# Arduinp-Shield-MicroPunch.net
KiCad netlist of a schematic drawn in EAGLE
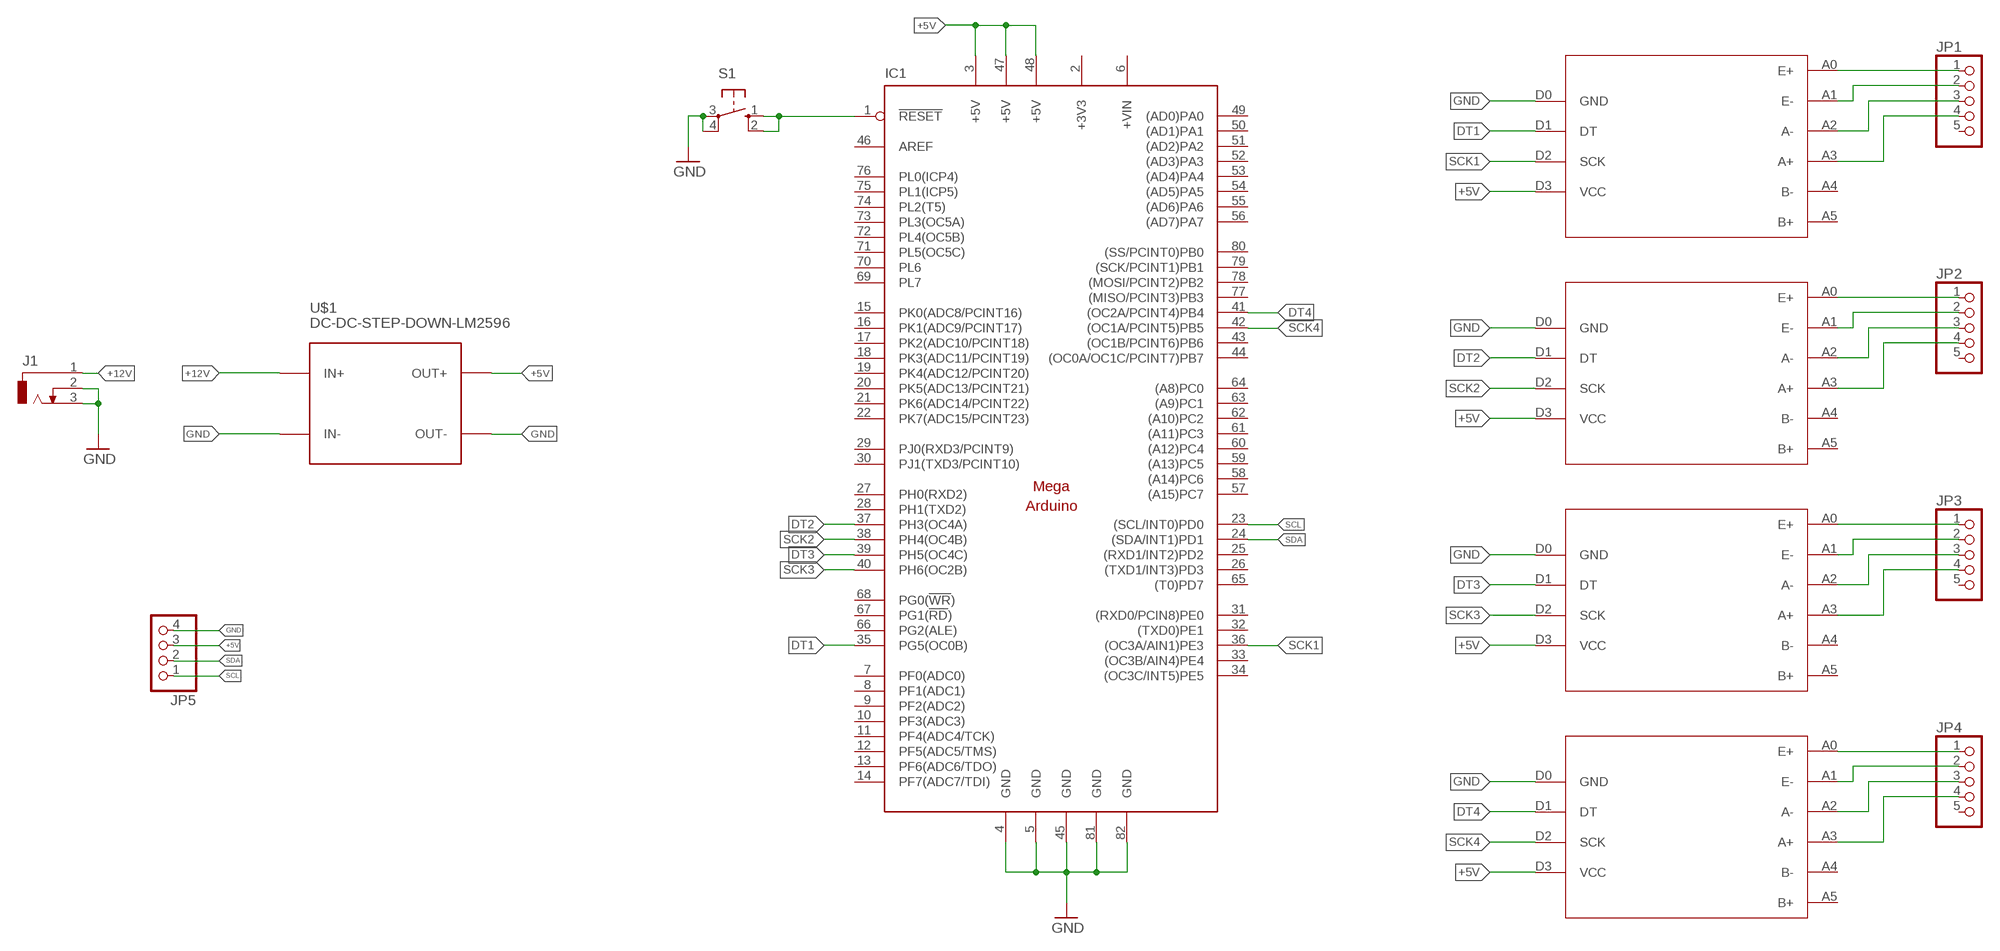
[diagram p0: schematic, sheet 1]

(export (version "E")
  (design (tool "Eeschema 10.0.6"))
  (components
    (comp (ref "IC1")
      (value "MEGAARDUINO_11")
      (footprint "eagle-import:MEGA_ARDUINO_1")
      (libsource (lib "eagle-import") (part "MEGAARDUINO_11"))
    )
    (comp (ref "J1")
      (value "DCJ0303")
      (footprint "eagle-import:DCJ0303")
      (libsource (lib "eagle-import") (part "DCJ0303"))
    )
    (comp (ref "JP1")
      (value "PINHD-1X5")
      (footprint "eagle-import:1X05")
      (libsource (lib "eagle-import") (part "PINHD-1X5"))
    )
    (comp (ref "JP2")
      (value "PINHD-1X5")
      (footprint "eagle-import:1X05")
      (libsource (lib "eagle-import") (part "PINHD-1X5"))
    )
    (comp (ref "JP3")
      (value "PINHD-1X5")
      (footprint "eagle-import:1X05")
      (libsource (lib "eagle-import") (part "PINHD-1X5"))
    )
    (comp (ref "JP4")
      (value "PINHD-1X5")
      (footprint "eagle-import:1X05")
      (libsource (lib "eagle-import") (part "PINHD-1X5"))
    )
    (comp (ref "JP5")
      (value "PINHD-1X4")
      (footprint "eagle-import:1X04")
      (libsource (lib "eagle-import") (part "PINHD-1X4"))
    )
    (comp (ref "S1")
      (value "10-XX")
      (footprint "eagle-import:B3F-10XX")
      (fields (field (name "MPN") "B3F-1000"))
      (libsource (lib "eagle-import") (part "10-XX"))
    )
    (comp (ref "SM1")
      (value "HX711")
      (footprint "eagle-import:HX711")
      (libsource (lib "eagle-import") (part "HX711"))
    )
    (comp (ref "SM2")
      (value "HX711")
      (footprint "eagle-import:HX711")
      (libsource (lib "eagle-import") (part "HX711"))
    )
    (comp (ref "SM3")
      (value "HX711")
      (footprint "eagle-import:HX711")
      (libsource (lib "eagle-import") (part "HX711"))
    )
    (comp (ref "SM4")
      (value "HX711")
      (footprint "eagle-import:HX711")
      (libsource (lib "eagle-import") (part "HX711"))
    )
    (comp (ref "U$1")
      (value "DC-DC-STEP-DOWN-LM2596")
      (footprint "eagle-import:DC-DC-STEP-DOWN-LM2596")
      (libsource (lib "eagle-import") (part "DC-DC-STEP-DOWN-LM2596"))
    )
  )
  (nets
    (net (code "1") (name "+5V") (class "Default")
      (node (ref "IC1") (pin "3") (pinfunction "+5V_3") (pintype "power_in"))
      (node (ref "IC1") (pin "47") (pinfunction "+5V_47") (pintype "power_in"))
      (node (ref "IC1") (pin "48") (pinfunction "+5V_48") (pintype "power_in"))
      (node (ref "JP5") (pin "3") (pinfunction "3_3") (pintype "passive"))
      (node (ref "SM1") (pin "D3") (pinfunction "VCC_D3") (pintype "bidirectional"))
      (node (ref "SM2") (pin "D3") (pinfunction "VCC_D3") (pintype "bidirectional"))
      (node (ref "SM3") (pin "D3") (pinfunction "VCC_D3") (pintype "bidirectional"))
      (node (ref "SM4") (pin "D3") (pinfunction "VCC_D3") (pintype "bidirectional"))
      (node (ref "U$1") (pin "OUT+") (pinfunction "OUT+_OUT+") (pintype "bidirectional"))
    )
    (net (code "2") (name "+12V") (class "Default")
      (node (ref "J1") (pin "1") (pinfunction "1_1") (pintype "passive"))
      (node (ref "U$1") (pin "IN+") (pinfunction "IN+_IN+") (pintype "bidirectional"))
    )
    (net (code "3") (name "/+3V3") (class "Default")
      (node (ref "IC1") (pin "2") (pinfunction "+3V3_2") (pintype "power_in"))
    )
    (net (code "4") (name "/+VIN") (class "Default")
      (node (ref "IC1") (pin "6") (pinfunction "+VIN_6") (pintype "power_in"))
    )
    (net (code "5") (name "DT1") (class "Default")
      (node (ref "IC1") (pin "35") (pinfunction "PG5(OC0B)_35") (pintype "bidirectional"))
      (node (ref "SM1") (pin "D1") (pinfunction "DT_D1") (pintype "bidirectional"))
    )
    (net (code "6") (name "DT2") (class "Default")
      (node (ref "IC1") (pin "37") (pinfunction "PH3(OC4A)_37") (pintype "bidirectional"))
      (node (ref "SM2") (pin "D1") (pinfunction "DT_D1") (pintype "bidirectional"))
    )
    (net (code "7") (name "DT3") (class "Default")
      (node (ref "IC1") (pin "39") (pinfunction "PH5(OC4C)_39") (pintype "bidirectional"))
      (node (ref "SM3") (pin "D1") (pinfunction "DT_D1") (pintype "bidirectional"))
    )
    (net (code "8") (name "DT4") (class "Default")
      (node (ref "IC1") (pin "41") (pinfunction "(OC2A/PCINT4)PB4_41") (pintype "bidirectional"))
      (node (ref "SM4") (pin "D1") (pinfunction "DT_D1") (pintype "bidirectional"))
    )
    (net (code "9") (name "GND") (class "Default")
      (node (ref "IC1") (pin "4") (pinfunction "GND_4") (pintype "power_in"))
      (node (ref "IC1") (pin "45") (pinfunction "GND_45") (pintype "power_in"))
      (node (ref "IC1") (pin "5") (pinfunction "GND_5") (pintype "power_in"))
      (node (ref "IC1") (pin "81") (pinfunction "GND_81") (pintype "power_in"))
      (node (ref "IC1") (pin "82") (pinfunction "GND_82") (pintype "power_in"))
      (node (ref "J1") (pin "2") (pinfunction "2_2") (pintype "passive"))
      (node (ref "J1") (pin "3") (pinfunction "3_3") (pintype "passive"))
      (node (ref "JP5") (pin "4") (pinfunction "4_4") (pintype "passive"))
      (node (ref "S1") (pin "3") (pinfunction "P_3") (pintype "passive"))
      (node (ref "S1") (pin "4") (pinfunction "P1_4") (pintype "passive"))
      (node (ref "SM1") (pin "D0") (pinfunction "GND_D0") (pintype "bidirectional"))
      (node (ref "SM2") (pin "D0") (pinfunction "GND_D0") (pintype "bidirectional"))
      (node (ref "SM3") (pin "D0") (pinfunction "GND_D0") (pintype "bidirectional"))
      (node (ref "SM4") (pin "D0") (pinfunction "GND_D0") (pintype "bidirectional"))
      (node (ref "U$1") (pin "IN-") (pinfunction "IN-_IN-") (pintype "bidirectional"))
      (node (ref "U$1") (pin "OUT-") (pinfunction "OUT-_OUT-") (pintype "bidirectional"))
    )
    (net (code "10") (name "Net-(IC1-~{RESET})") (class "Default")
      (node (ref "IC1") (pin "1") (pinfunction "~{RESET}_1") (pintype "bidirectional"))
      (node (ref "S1") (pin "1") (pinfunction "S_1") (pintype "passive"))
      (node (ref "S1") (pin "2") (pinfunction "S1_2") (pintype "passive"))
    )
    (net (code "11") (name "Net-(SM1-A+)") (class "Default")
      (node (ref "JP1") (pin "4") (pinfunction "4_4") (pintype "passive"))
      (node (ref "SM1") (pin "A3") (pinfunction "A+_A3") (pintype "bidirectional"))
    )
    (net (code "12") (name "Net-(SM1-A-)") (class "Default")
      (node (ref "JP1") (pin "3") (pinfunction "3_3") (pintype "passive"))
      (node (ref "SM1") (pin "A2") (pinfunction "A-_A2") (pintype "bidirectional"))
    )
    (net (code "13") (name "Net-(SM1-E+)") (class "Default")
      (node (ref "JP1") (pin "1") (pinfunction "1_1") (pintype "passive"))
      (node (ref "SM1") (pin "A0") (pinfunction "E+_A0") (pintype "bidirectional"))
    )
    (net (code "14") (name "Net-(SM1-E-)") (class "Default")
      (node (ref "JP1") (pin "2") (pinfunction "2_2") (pintype "passive"))
      (node (ref "SM1") (pin "A1") (pinfunction "E-_A1") (pintype "bidirectional"))
    )
    (net (code "15") (name "Net-(SM2-A+)") (class "Default")
      (node (ref "JP2") (pin "4") (pinfunction "4_4") (pintype "passive"))
      (node (ref "SM2") (pin "A3") (pinfunction "A+_A3") (pintype "bidirectional"))
    )
    (net (code "16") (name "Net-(SM2-A-)") (class "Default")
      (node (ref "JP2") (pin "3") (pinfunction "3_3") (pintype "passive"))
      (node (ref "SM2") (pin "A2") (pinfunction "A-_A2") (pintype "bidirectional"))
    )
    (net (code "17") (name "Net-(SM2-E+)") (class "Default")
      (node (ref "JP2") (pin "1") (pinfunction "1_1") (pintype "passive"))
      (node (ref "SM2") (pin "A0") (pinfunction "E+_A0") (pintype "bidirectional"))
    )
    (net (code "18") (name "Net-(SM2-E-)") (class "Default")
      (node (ref "JP2") (pin "2") (pinfunction "2_2") (pintype "passive"))
      (node (ref "SM2") (pin "A1") (pinfunction "E-_A1") (pintype "bidirectional"))
    )
    (net (code "19") (name "Net-(SM3-A+)") (class "Default")
      (node (ref "JP3") (pin "4") (pinfunction "4_4") (pintype "passive"))
      (node (ref "SM3") (pin "A3") (pinfunction "A+_A3") (pintype "bidirectional"))
    )
    (net (code "20") (name "Net-(SM3-A-)") (class "Default")
      (node (ref "JP3") (pin "3") (pinfunction "3_3") (pintype "passive"))
      (node (ref "SM3") (pin "A2") (pinfunction "A-_A2") (pintype "bidirectional"))
    )
    (net (code "21") (name "Net-(SM3-E+)") (class "Default")
      (node (ref "JP3") (pin "1") (pinfunction "1_1") (pintype "passive"))
      (node (ref "SM3") (pin "A0") (pinfunction "E+_A0") (pintype "bidirectional"))
    )
    (net (code "22") (name "Net-(SM3-E-)") (class "Default")
      (node (ref "JP3") (pin "2") (pinfunction "2_2") (pintype "passive"))
      (node (ref "SM3") (pin "A1") (pinfunction "E-_A1") (pintype "bidirectional"))
    )
    (net (code "23") (name "Net-(SM4-A+)") (class "Default")
      (node (ref "JP4") (pin "4") (pinfunction "4_4") (pintype "passive"))
      (node (ref "SM4") (pin "A3") (pinfunction "A+_A3") (pintype "bidirectional"))
    )
    (net (code "24") (name "Net-(SM4-A-)") (class "Default")
      (node (ref "JP4") (pin "3") (pinfunction "3_3") (pintype "passive"))
      (node (ref "SM4") (pin "A2") (pinfunction "A-_A2") (pintype "bidirectional"))
    )
    (net (code "25") (name "Net-(SM4-E+)") (class "Default")
      (node (ref "JP4") (pin "1") (pinfunction "1_1") (pintype "passive"))
      (node (ref "SM4") (pin "A0") (pinfunction "E+_A0") (pintype "bidirectional"))
    )
    (net (code "26") (name "Net-(SM4-E-)") (class "Default")
      (node (ref "JP4") (pin "2") (pinfunction "2_2") (pintype "passive"))
      (node (ref "SM4") (pin "A1") (pinfunction "E-_A1") (pintype "bidirectional"))
    )
    (net (code "27") (name "SCK1") (class "Default")
      (node (ref "IC1") (pin "36") (pinfunction "(OC3A/AIN1)PE3_36") (pintype "bidirectional"))
      (node (ref "SM1") (pin "D2") (pinfunction "SCK_D2") (pintype "bidirectional"))
    )
    (net (code "28") (name "SCK2") (class "Default")
      (node (ref "IC1") (pin "38") (pinfunction "PH4(OC4B)_38") (pintype "bidirectional"))
      (node (ref "SM2") (pin "D2") (pinfunction "SCK_D2") (pintype "bidirectional"))
    )
    (net (code "29") (name "SCK3") (class "Default")
      (node (ref "IC1") (pin "40") (pinfunction "PH6(OC2B)_40") (pintype "bidirectional"))
      (node (ref "SM3") (pin "D2") (pinfunction "SCK_D2") (pintype "bidirectional"))
    )
    (net (code "30") (name "SCK4") (class "Default")
      (node (ref "IC1") (pin "42") (pinfunction "(OC1A/PCINT5)PB5_42") (pintype "bidirectional"))
      (node (ref "SM4") (pin "D2") (pinfunction "SCK_D2") (pintype "bidirectional"))
    )
    (net (code "31") (name "SCL") (class "Default")
      (node (ref "IC1") (pin "23") (pinfunction "(SCL/INT0)PD0_23") (pintype "bidirectional"))
      (node (ref "JP5") (pin "1") (pinfunction "1_1") (pintype "passive"))
    )
    (net (code "32") (name "SDA") (class "Default")
      (node (ref "IC1") (pin "24") (pinfunction "(SDA/INT1)PD1_24") (pintype "bidirectional"))
      (node (ref "JP5") (pin "2") (pinfunction "2_2") (pintype "passive"))
    )
    (net (code "33") (name "unconnected-(IC1-(A8)PC0-Pad64)") (class "Default")
      (node (ref "IC1") (pin "64") (pinfunction "(A8)PC0_64") (pintype "bidirectional"))
    )
    (net (code "34") (name "unconnected-(IC1-(A9)PC1-Pad63)") (class "Default")
      (node (ref "IC1") (pin "63") (pinfunction "(A9)PC1_63") (pintype "bidirectional"))
    )
    (net (code "35") (name "unconnected-(IC1-(A10)PC2-Pad62)") (class "Default")
      (node (ref "IC1") (pin "62") (pinfunction "(A10)PC2_62") (pintype "bidirectional"))
    )
    (net (code "36") (name "unconnected-(IC1-(A11)PC3-Pad61)") (class "Default")
      (node (ref "IC1") (pin "61") (pinfunction "(A11)PC3_61") (pintype "bidirectional"))
    )
    (net (code "37") (name "unconnected-(IC1-(A12)PC4-Pad60)") (class "Default")
      (node (ref "IC1") (pin "60") (pinfunction "(A12)PC4_60") (pintype "bidirectional"))
    )
    (net (code "38") (name "unconnected-(IC1-(A13)PC5-Pad59)") (class "Default")
      (node (ref "IC1") (pin "59") (pinfunction "(A13)PC5_59") (pintype "bidirectional"))
    )
    (net (code "39") (name "unconnected-(IC1-(A14)PC6-Pad58)") (class "Default")
      (node (ref "IC1") (pin "58") (pinfunction "(A14)PC6_58") (pintype "bidirectional"))
    )
    (net (code "40") (name "unconnected-(IC1-(A15)PC7-Pad57)") (class "Default")
      (node (ref "IC1") (pin "57") (pinfunction "(A15)PC7_57") (pintype "bidirectional"))
    )
    (net (code "41") (name "unconnected-(IC1-(AD0)PA0-Pad49)") (class "Default")
      (node (ref "IC1") (pin "49") (pinfunction "(AD0)PA0_49") (pintype "bidirectional"))
    )
    (net (code "42") (name "unconnected-(IC1-(AD1)PA1-Pad50)") (class "Default")
      (node (ref "IC1") (pin "50") (pinfunction "(AD1)PA1_50") (pintype "bidirectional"))
    )
    (net (code "43") (name "unconnected-(IC1-(AD2)PA2-Pad51)") (class "Default")
      (node (ref "IC1") (pin "51") (pinfunction "(AD2)PA2_51") (pintype "bidirectional"))
    )
    (net (code "44") (name "unconnected-(IC1-(AD3)PA3-Pad52)") (class "Default")
      (node (ref "IC1") (pin "52") (pinfunction "(AD3)PA3_52") (pintype "bidirectional"))
    )
    (net (code "45") (name "unconnected-(IC1-(AD4)PA4-Pad53)") (class "Default")
      (node (ref "IC1") (pin "53") (pinfunction "(AD4)PA4_53") (pintype "bidirectional"))
    )
    (net (code "46") (name "unconnected-(IC1-(AD5)PA5-Pad54)") (class "Default")
      (node (ref "IC1") (pin "54") (pinfunction "(AD5)PA5_54") (pintype "bidirectional"))
    )
    (net (code "47") (name "unconnected-(IC1-(AD6)PA6-Pad55)") (class "Default")
      (node (ref "IC1") (pin "55") (pinfunction "(AD6)PA6_55") (pintype "bidirectional"))
    )
    (net (code "48") (name "unconnected-(IC1-(AD7)PA7-Pad56)") (class "Default")
      (node (ref "IC1") (pin "56") (pinfunction "(AD7)PA7_56") (pintype "bidirectional"))
    )
    (net (code "49") (name "unconnected-(IC1-(MISO{slash}PCINT3)PB3-Pad77)") (class "Default")
      (node (ref "IC1") (pin "77") (pinfunction "(MISO/PCINT3)PB3_77") (pintype "bidirectional"))
    )
    (net (code "50") (name "unconnected-(IC1-(MOSI{slash}PCINT2)PB2-Pad78)") (class "Default")
      (node (ref "IC1") (pin "78") (pinfunction "(MOSI/PCINT2)PB2_78") (pintype "bidirectional"))
    )
    (net (code "51") (name "unconnected-(IC1-(OC0A{slash}OC1C{slash}PCINT7)PB7-Pad44)") (class "Default")
      (node (ref "IC1") (pin "44") (pinfunction "(OC0A/OC1C/PCINT7)PB7_44") (pintype "bidirectional"))
    )
    (net (code "52") (name "unconnected-(IC1-(OC1B{slash}PCINT6)PB6-Pad43)") (class "Default")
      (node (ref "IC1") (pin "43") (pinfunction "(OC1B/PCINT6)PB6_43") (pintype "bidirectional"))
    )
    (net (code "53") (name "unconnected-(IC1-(OC3B{slash}AIN4)PE4-Pad33)") (class "Default")
      (node (ref "IC1") (pin "33") (pinfunction "(OC3B/AIN4)PE4_33") (pintype "bidirectional"))
    )
    (net (code "54") (name "unconnected-(IC1-(OC3C{slash}INT5)PE5-Pad34)") (class "Default")
      (node (ref "IC1") (pin "34") (pinfunction "(OC3C/INT5)PE5_34") (pintype "bidirectional"))
    )
    (net (code "55") (name "unconnected-(IC1-(RXD0{slash}PCIN8)PE0-Pad31)") (class "Default")
      (node (ref "IC1") (pin "31") (pinfunction "(RXD0/PCIN8)PE0_31") (pintype "bidirectional"))
    )
    (net (code "56") (name "unconnected-(IC1-(RXD1{slash}INT2)PD2-Pad25)") (class "Default")
      (node (ref "IC1") (pin "25") (pinfunction "(RXD1/INT2)PD2_25") (pintype "bidirectional"))
    )
    (net (code "57") (name "unconnected-(IC1-(SCK{slash}PCINT1)PB1-Pad79)") (class "Default")
      (node (ref "IC1") (pin "79") (pinfunction "(SCK/PCINT1)PB1_79") (pintype "bidirectional"))
    )
    (net (code "58") (name "unconnected-(IC1-(SS{slash}PCINT0)PB0-Pad80)") (class "Default")
      (node (ref "IC1") (pin "80") (pinfunction "(SS/PCINT0)PB0_80") (pintype "bidirectional"))
    )
    (net (code "59") (name "unconnected-(IC1-(T0)PD7-Pad65)") (class "Default")
      (node (ref "IC1") (pin "65") (pinfunction "(T0)PD7_65") (pintype "bidirectional"))
    )
    (net (code "60") (name "unconnected-(IC1-(TXD0)PE1-Pad32)") (class "Default")
      (node (ref "IC1") (pin "32") (pinfunction "(TXD0)PE1_32") (pintype "bidirectional"))
    )
    (net (code "61") (name "unconnected-(IC1-(TXD1{slash}INT3)PD3-Pad26)") (class "Default")
      (node (ref "IC1") (pin "26") (pinfunction "(TXD1/INT3)PD3_26") (pintype "bidirectional"))
    )
    (net (code "62") (name "unconnected-(IC1-AREF-Pad46)") (class "Default")
      (node (ref "IC1") (pin "46") (pinfunction "AREF_46") (pintype "bidirectional"))
    )
    (net (code "63") (name "unconnected-(IC1-PF0(ADC0)-Pad7)") (class "Default")
      (node (ref "IC1") (pin "7") (pinfunction "PF0(ADC0)_7") (pintype "bidirectional"))
    )
    (net (code "64") (name "unconnected-(IC1-PF1(ADC1)-Pad8)") (class "Default")
      (node (ref "IC1") (pin "8") (pinfunction "PF1(ADC1)_8") (pintype "bidirectional"))
    )
    (net (code "65") (name "unconnected-(IC1-PF2(ADC2)-Pad9)") (class "Default")
      (node (ref "IC1") (pin "9") (pinfunction "PF2(ADC2)_9") (pintype "bidirectional"))
    )
    (net (code "66") (name "unconnected-(IC1-PF3(ADC3)-Pad10)") (class "Default")
      (node (ref "IC1") (pin "10") (pinfunction "PF3(ADC3)_10") (pintype "bidirectional"))
    )
    (net (code "67") (name "unconnected-(IC1-PF4(ADC4{slash}TCK)-Pad11)") (class "Default")
      (node (ref "IC1") (pin "11") (pinfunction "PF4(ADC4/TCK)_11") (pintype "bidirectional"))
    )
    (net (code "68") (name "unconnected-(IC1-PF5(ADC5{slash}TMS)-Pad12)") (class "Default")
      (node (ref "IC1") (pin "12") (pinfunction "PF5(ADC5/TMS)_12") (pintype "bidirectional"))
    )
    (net (code "69") (name "unconnected-(IC1-PF6(ADC6{slash}TDO)-Pad13)") (class "Default")
      (node (ref "IC1") (pin "13") (pinfunction "PF6(ADC6/TDO)_13") (pintype "bidirectional"))
    )
    (net (code "70") (name "unconnected-(IC1-PF7(ADC7{slash}TDI)-Pad14)") (class "Default")
      (node (ref "IC1") (pin "14") (pinfunction "PF7(ADC7/TDI)_14") (pintype "bidirectional"))
    )
    (net (code "71") (name "unconnected-(IC1-PG0(~{WR})-Pad68)") (class "Default")
      (node (ref "IC1") (pin "68") (pinfunction "PG0(~{WR})_68") (pintype "bidirectional"))
    )
    (net (code "72") (name "unconnected-(IC1-PG1(~{RD})-Pad67)") (class "Default")
      (node (ref "IC1") (pin "67") (pinfunction "PG1(~{RD})_67") (pintype "bidirectional"))
    )
    (net (code "73") (name "unconnected-(IC1-PG2(ALE)-Pad66)") (class "Default")
      (node (ref "IC1") (pin "66") (pinfunction "PG2(ALE)_66") (pintype "bidirectional"))
    )
    (net (code "74") (name "unconnected-(IC1-PH0(RXD2)-Pad27)") (class "Default")
      (node (ref "IC1") (pin "27") (pinfunction "PH0(RXD2)_27") (pintype "bidirectional"))
    )
    (net (code "75") (name "unconnected-(IC1-PH1(TXD2)-Pad28)") (class "Default")
      (node (ref "IC1") (pin "28") (pinfunction "PH1(TXD2)_28") (pintype "bidirectional"))
    )
    (net (code "76") (name "unconnected-(IC1-PJ0(RXD3{slash}PCINT9)-Pad29)") (class "Default")
      (node (ref "IC1") (pin "29") (pinfunction "PJ0(RXD3/PCINT9)_29") (pintype "bidirectional"))
    )
    (net (code "77") (name "unconnected-(IC1-PJ1(TXD3{slash}PCINT10)-Pad30)") (class "Default")
      (node (ref "IC1") (pin "30") (pinfunction "PJ1(TXD3/PCINT10)_30") (pintype "bidirectional"))
    )
    (net (code "78") (name "unconnected-(IC1-PK0(ADC8{slash}PCINT16)-Pad15)") (class "Default")
      (node (ref "IC1") (pin "15") (pinfunction "PK0(ADC8/PCINT16)_15") (pintype "bidirectional"))
    )
    (net (code "79") (name "unconnected-(IC1-PK1(ADC9{slash}PCINT17)-Pad16)") (class "Default")
      (node (ref "IC1") (pin "16") (pinfunction "PK1(ADC9/PCINT17)_16") (pintype "bidirectional"))
    )
    (net (code "80") (name "unconnected-(IC1-PK2(ADC10{slash}PCINT18)-Pad17)") (class "Default")
      (node (ref "IC1") (pin "17") (pinfunction "PK2(ADC10/PCINT18)_17") (pintype "bidirectional"))
    )
    (net (code "81") (name "unconnected-(IC1-PK3(ADC11{slash}PCINT19)-Pad18)") (class "Default")
      (node (ref "IC1") (pin "18") (pinfunction "PK3(ADC11/PCINT19)_18") (pintype "bidirectional"))
    )
    (net (code "82") (name "unconnected-(IC1-PK4(ADC12{slash}PCINT20)-Pad19)") (class "Default")
      (node (ref "IC1") (pin "19") (pinfunction "PK4(ADC12/PCINT20)_19") (pintype "bidirectional"))
    )
    (net (code "83") (name "unconnected-(IC1-PK5(ADC13{slash}PCINT21)-Pad20)") (class "Default")
      (node (ref "IC1") (pin "20") (pinfunction "PK5(ADC13/PCINT21)_20") (pintype "bidirectional"))
    )
    (net (code "84") (name "unconnected-(IC1-PK6(ADC14{slash}PCINT22)-Pad21)") (class "Default")
      (node (ref "IC1") (pin "21") (pinfunction "PK6(ADC14/PCINT22)_21") (pintype "bidirectional"))
    )
    (net (code "85") (name "unconnected-(IC1-PK7(ADC15{slash}PCINT23)-Pad22)") (class "Default")
      (node (ref "IC1") (pin "22") (pinfunction "PK7(ADC15/PCINT23)_22") (pintype "bidirectional"))
    )
    (net (code "86") (name "unconnected-(IC1-PL0(ICP4)-Pad76)") (class "Default")
      (node (ref "IC1") (pin "76") (pinfunction "PL0(ICP4)_76") (pintype "bidirectional"))
    )
    (net (code "87") (name "unconnected-(IC1-PL1(ICP5)-Pad75)") (class "Default")
      (node (ref "IC1") (pin "75") (pinfunction "PL1(ICP5)_75") (pintype "bidirectional"))
    )
    (net (code "88") (name "unconnected-(IC1-PL2(T5)-Pad74)") (class "Default")
      (node (ref "IC1") (pin "74") (pinfunction "PL2(T5)_74") (pintype "bidirectional"))
    )
    (net (code "89") (name "unconnected-(IC1-PL3(OC5A)-Pad73)") (class "Default")
      (node (ref "IC1") (pin "73") (pinfunction "PL3(OC5A)_73") (pintype "bidirectional"))
    )
    (net (code "90") (name "unconnected-(IC1-PL4(OC5B)-Pad72)") (class "Default")
      (node (ref "IC1") (pin "72") (pinfunction "PL4(OC5B)_72") (pintype "bidirectional"))
    )
    (net (code "91") (name "unconnected-(IC1-PL5(OC5C)-Pad71)") (class "Default")
      (node (ref "IC1") (pin "71") (pinfunction "PL5(OC5C)_71") (pintype "bidirectional"))
    )
    (net (code "92") (name "unconnected-(IC1-PL6-Pad70)") (class "Default")
      (node (ref "IC1") (pin "70") (pinfunction "PL6_70") (pintype "bidirectional"))
    )
    (net (code "93") (name "unconnected-(IC1-PL7-Pad69)") (class "Default")
      (node (ref "IC1") (pin "69") (pinfunction "PL7_69") (pintype "bidirectional"))
    )
    (net (code "94") (name "unconnected-(JP1-Pad5)") (class "Default")
      (node (ref "JP1") (pin "5") (pinfunction "5_5") (pintype "passive"))
    )
    (net (code "95") (name "unconnected-(JP2-Pad5)") (class "Default")
      (node (ref "JP2") (pin "5") (pinfunction "5_5") (pintype "passive"))
    )
    (net (code "96") (name "unconnected-(JP3-Pad5)") (class "Default")
      (node (ref "JP3") (pin "5") (pinfunction "5_5") (pintype "passive"))
    )
    (net (code "97") (name "unconnected-(JP4-Pad5)") (class "Default")
      (node (ref "JP4") (pin "5") (pinfunction "5_5") (pintype "passive"))
    )
    (net (code "98") (name "unconnected-(SM1-B+-PadA5)") (class "Default")
      (node (ref "SM1") (pin "A5") (pinfunction "B+_A5") (pintype "bidirectional"))
    )
    (net (code "99") (name "unconnected-(SM1-B--PadA4)") (class "Default")
      (node (ref "SM1") (pin "A4") (pinfunction "B-_A4") (pintype "bidirectional"))
    )
    (net (code "100") (name "unconnected-(SM2-B+-PadA5)") (class "Default")
      (node (ref "SM2") (pin "A5") (pinfunction "B+_A5") (pintype "bidirectional"))
    )
    (net (code "101") (name "unconnected-(SM2-B--PadA4)") (class "Default")
      (node (ref "SM2") (pin "A4") (pinfunction "B-_A4") (pintype "bidirectional"))
    )
    (net (code "102") (name "unconnected-(SM3-B+-PadA5)") (class "Default")
      (node (ref "SM3") (pin "A5") (pinfunction "B+_A5") (pintype "bidirectional"))
    )
    (net (code "103") (name "unconnected-(SM3-B--PadA4)") (class "Default")
      (node (ref "SM3") (pin "A4") (pinfunction "B-_A4") (pintype "bidirectional"))
    )
    (net (code "104") (name "unconnected-(SM4-B+-PadA5)") (class "Default")
      (node (ref "SM4") (pin "A5") (pinfunction "B+_A5") (pintype "bidirectional"))
    )
    (net (code "105") (name "unconnected-(SM4-B--PadA4)") (class "Default")
      (node (ref "SM4") (pin "A4") (pinfunction "B-_A4") (pintype "bidirectional"))
    )
  )
)
